# Power_input.net
KiCad netlist of a schematic drawn in Altium Designer
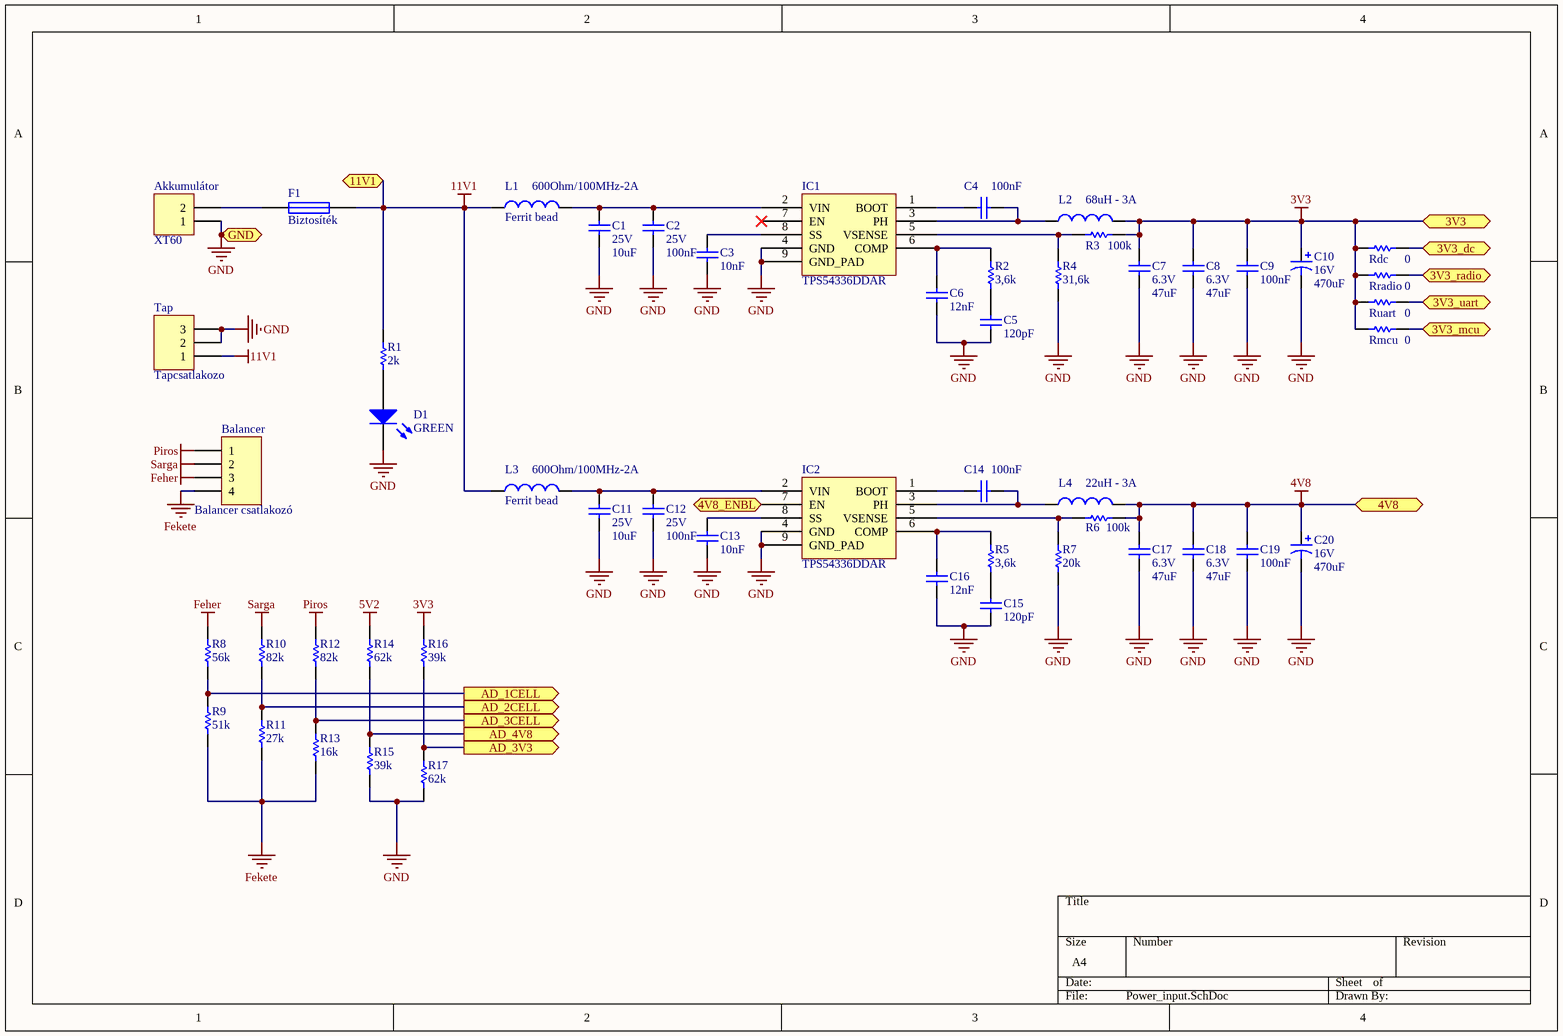
[diagram p0: Power_input.SchDoc]

(export (version "E")
  (design (tool "Eeschema 10.0.6"))
  (components
    (comp (ref "Akkumulátor")
      (value "XT60")
      (footprint "XT60")
      (description "Header, 2-Pin")
      (fields (field (name "PUBLISHER") "Altium Limited"))
      (libsource (lib "Miscellaneous Connectors") (part "Header 2"))
    )
    (comp (ref "Balancer")
      (value "Balancer csatlakozó")
      (footprint "FP_CONN4_TUSKE_254MM")
      (description "Header, 4-Pin")
      (fields (field (name "PUBLISHER") "Altium Limited"))
      (libsource (lib "Miscellaneous Connectors") (part "Header 4"))
    )
    (comp (ref "C1")
      (value "25V")
      (footprint "FP_1206_CAP_125")
      (description "Capacitor")
      (fields (field (name "ALTIUM_VALUE") "10uF") (field (name "PUBLISHER") "Altium Limited"))
      (libsource (lib "Miscellaneous Devices") (part "Cap"))
    )
    (comp (ref "C2")
      (value "25V")
      (footprint "FP_1206_CAP_125")
      (description "Capacitor")
      (fields (field (name "ALTIUM_VALUE") "100nF") (field (name "PUBLISHER") "Altium Limited"))
      (libsource (lib "Miscellaneous Devices") (part "Cap"))
    )
    (comp (ref "C3")
      (value "10nF")
      (footprint "FP_0603_CAP_080")
      (description "Capacitor")
      (fields (field (name "Comment") "Cap") (field (name "PUBLISHER") "Altium Limited"))
      (libsource (lib "Miscellaneous Devices") (part "Cap"))
    )
    (comp (ref "C4")
      (value "100nF")
      (footprint "FP_1206_CAP_125")
      (description "Capacitor")
      (fields (field (name "Comment") "Cap") (field (name "PUBLISHER") "Altium Limited"))
      (libsource (lib "Miscellaneous Devices") (part "Cap"))
    )
    (comp (ref "C5")
      (value "120pF")
      (footprint "FP_0603_CAP_080")
      (description "Capacitor")
      (fields (field (name "PUBLISHER") "Altium Limited"))
      (libsource (lib "Miscellaneous Devices") (part "Cap"))
    )
    (comp (ref "C6")
      (value "12nF")
      (footprint "FP_0603_CAP_080")
      (description "Capacitor")
      (fields (field (name "PUBLISHER") "Altium Limited"))
      (libsource (lib "Miscellaneous Devices") (part "Cap"))
    )
    (comp (ref "C7")
      (value "6.3V")
      (footprint "FP_1206_CAP_125")
      (description "Capacitor")
      (fields (field (name "ALTIUM_VALUE") "47uF") (field (name "PUBLISHER") "Altium Limited"))
      (libsource (lib "Miscellaneous Devices") (part "Cap"))
    )
    (comp (ref "C8")
      (value "6.3V")
      (footprint "FP_1206_CAP_125")
      (description "Capacitor")
      (fields (field (name "ALTIUM_VALUE") "47uF") (field (name "PUBLISHER") "Altium Limited"))
      (libsource (lib "Miscellaneous Devices") (part "Cap"))
    )
    (comp (ref "C9")
      (value "100nF")
      (footprint "FP_1206_CAP_125")
      (description "Capacitor")
      (fields (field (name "Comment") "Cap") (field (name "PUBLISHER") "Altium Limited"))
      (libsource (lib "Miscellaneous Devices") (part "Cap"))
    )
    (comp (ref "C10")
      (value "16V")
      (footprint "power_cap_10mm")
      (description "Polarized Capacitor (Radial)")
      (fields (field (name "ALTIUM_VALUE") "470uF") (field (name "PUBLISHER") "Altium Limited"))
      (libsource (lib "Miscellaneous Devices") (part "Cap Pol1"))
    )
    (comp (ref "C11")
      (value "25V")
      (footprint "FP_1206_CAP_125")
      (description "Capacitor")
      (fields (field (name "ALTIUM_VALUE") "10uF") (field (name "PUBLISHER") "Altium Limited"))
      (libsource (lib "Miscellaneous Devices") (part "Cap"))
    )
    (comp (ref "C12")
      (value "25V")
      (footprint "FP_1206_CAP_125")
      (description "Capacitor")
      (fields (field (name "ALTIUM_VALUE") "100nF") (field (name "PUBLISHER") "Altium Limited"))
      (libsource (lib "Miscellaneous Devices") (part "Cap"))
    )
    (comp (ref "C13")
      (value "10nF")
      (footprint "FP_0603_CAP_080")
      (description "Capacitor")
      (fields (field (name "Comment") "Cap") (field (name "PUBLISHER") "Altium Limited"))
      (libsource (lib "Miscellaneous Devices") (part "Cap"))
    )
    (comp (ref "C14")
      (value "100nF")
      (footprint "FP_1206_CAP_125")
      (description "Capacitor")
      (fields (field (name "Comment") "Cap") (field (name "PUBLISHER") "Altium Limited"))
      (libsource (lib "Miscellaneous Devices") (part "Cap"))
    )
    (comp (ref "C15")
      (value "120pF")
      (footprint "FP_0603_CAP_080")
      (description "Capacitor")
      (fields (field (name "PUBLISHER") "Altium Limited"))
      (libsource (lib "Miscellaneous Devices") (part "Cap"))
    )
    (comp (ref "C16")
      (value "12nF")
      (footprint "FP_0603_CAP_080")
      (description "Capacitor")
      (fields (field (name "PUBLISHER") "Altium Limited"))
      (libsource (lib "Miscellaneous Devices") (part "Cap"))
    )
    (comp (ref "C17")
      (value "6.3V")
      (footprint "FP_1206_CAP_125")
      (description "Capacitor")
      (fields (field (name "ALTIUM_VALUE") "47uF") (field (name "PUBLISHER") "Altium Limited"))
      (libsource (lib "Miscellaneous Devices") (part "Cap"))
    )
    (comp (ref "C18")
      (value "6.3V")
      (footprint "FP_1206_CAP_125")
      (description "Capacitor")
      (fields (field (name "ALTIUM_VALUE") "47uF") (field (name "PUBLISHER") "Altium Limited"))
      (libsource (lib "Miscellaneous Devices") (part "Cap"))
    )
    (comp (ref "C19")
      (value "100nF")
      (footprint "FP_1206_CAP_125")
      (description "Capacitor")
      (fields (field (name "Comment") "Cap") (field (name "PUBLISHER") "Altium Limited"))
      (libsource (lib "Miscellaneous Devices") (part "Cap"))
    )
    (comp (ref "C20")
      (value "16V")
      (footprint "power_cap_10mm")
      (description "Polarized Capacitor (Radial)")
      (fields (field (name "ALTIUM_VALUE") "470uF") (field (name "PUBLISHER") "Altium Limited"))
      (libsource (lib "Miscellaneous Devices") (part "Cap Pol1"))
    )
    (comp (ref "D1")
      (value "GREEN")
      (footprint "FP_1206_CAP_160")
      (description "Typical INFRARED GaAs LED")
      (fields (field (name "PUBLISHER") "Altium Limited"))
      (libsource (lib "Miscellaneous Devices") (part "LED0"))
    )
    (comp (ref "F1")
      (value "Biztosíték")
      (footprint "autosarus_foglalat")
      (description "Fuse")
      (fields (field (name "PUBLISHER") "Altium Limited"))
      (libsource (lib "Miscellaneous Devices") (part "Fuse 1"))
    )
    (comp (ref "IC1")
      (value "TPS54336DDAR")
      (footprint "SOIC8_thermal_pad")
      (libsource (lib "diploma") (part "TPS54336"))
    )
    (comp (ref "IC2")
      (value "TPS54336DDAR")
      (footprint "SOIC8_thermal_pad")
      (libsource (lib "diploma") (part "TPS54336"))
    )
    (comp (ref "L1")
      (value "Ferrit bead")
      (footprint "FP_0805_IND")
      (description "Inductor")
      (fields (field (name "ALTIUM_VALUE") "600Ohm/100MHz-2A") (field (name "PUBLISHER") "Altium Limited"))
      (libsource (lib "Miscellaneous Devices") (part "Inductor"))
    )
    (comp (ref "L2")
      (value "68uH - 3A")
      (footprint "power_inductor")
      (description "Inductor")
      (fields (field (name "PUBLISHER") "Altium Limited"))
      (libsource (lib "Miscellaneous Devices") (part "Inductor"))
    )
    (comp (ref "L3")
      (value "Ferrit bead")
      (footprint "FP_0805_IND")
      (description "Inductor")
      (fields (field (name "ALTIUM_VALUE") "600Ohm/100MHz-2A") (field (name "PUBLISHER") "Altium Limited"))
      (libsource (lib "Miscellaneous Devices") (part "Inductor"))
    )
    (comp (ref "L4")
      (value "22uH - 3A")
      (footprint "power_inductor")
      (description "Inductor")
      (fields (field (name "PUBLISHER") "Altium Limited"))
      (libsource (lib "Miscellaneous Devices") (part "Inductor"))
    )
    (comp (ref "R1")
      (value "2k")
      (footprint "FP_0603_RES")
      (description "Resistor")
      (fields (field (name "Comment") "Res1") (field (name "PUBLISHER") "Altium Limited"))
      (libsource (lib "Miscellaneous Devices") (part "Res1"))
    )
    (comp (ref "R2")
      (value "3,6k")
      (footprint "FP_0603_RES")
      (description "Resistor")
      (fields (field (name "Comment") "Res1") (field (name "PUBLISHER") "Altium Limited"))
      (libsource (lib "Miscellaneous Devices") (part "Res1"))
    )
    (comp (ref "R3")
      (value "100k")
      (footprint "FP_0603_RES")
      (description "Resistor")
      (fields (field (name "Comment") "Res1") (field (name "PUBLISHER") "Altium Limited"))
      (libsource (lib "Miscellaneous Devices") (part "Res1"))
    )
    (comp (ref "R4")
      (value "31,6k")
      (footprint "FP_0603_RES")
      (description "Resistor")
      (fields (field (name "Comment") "Res1") (field (name "PUBLISHER") "Altium Limited"))
      (libsource (lib "Miscellaneous Devices") (part "Res1"))
    )
    (comp (ref "R5")
      (value "3,6k")
      (footprint "FP_0603_RES")
      (description "Resistor")
      (fields (field (name "Comment") "Res1") (field (name "PUBLISHER") "Altium Limited"))
      (libsource (lib "Miscellaneous Devices") (part "Res1"))
    )
    (comp (ref "R6")
      (value "100k")
      (footprint "FP_0603_RES")
      (description "Resistor")
      (fields (field (name "Comment") "Res1") (field (name "PUBLISHER") "Altium Limited"))
      (libsource (lib "Miscellaneous Devices") (part "Res1"))
    )
    (comp (ref "R7")
      (value "20k")
      (footprint "FP_0603_RES")
      (description "Resistor")
      (fields (field (name "Comment") "Res1") (field (name "PUBLISHER") "Altium Limited"))
      (libsource (lib "Miscellaneous Devices") (part "Res1"))
    )
    (comp (ref "R8")
      (value "56k")
      (footprint "FP_0603_RES")
      (description "Resistor")
      (fields (field (name "Comment") "Res1") (field (name "PUBLISHER") "Altium Limited"))
      (libsource (lib "Miscellaneous Devices") (part "Res1"))
    )
    (comp (ref "R9")
      (value "51k")
      (footprint "FP_0603_RES")
      (description "Resistor")
      (fields (field (name "Comment") "Res1") (field (name "PUBLISHER") "Altium Limited"))
      (libsource (lib "Miscellaneous Devices") (part "Res1"))
    )
    (comp (ref "R10")
      (value "82k")
      (footprint "FP_0603_RES")
      (description "Resistor")
      (fields (field (name "Comment") "Res1") (field (name "PUBLISHER") "Altium Limited"))
      (libsource (lib "Miscellaneous Devices") (part "Res1"))
    )
    (comp (ref "R11")
      (value "27k")
      (footprint "FP_0603_RES")
      (description "Resistor")
      (fields (field (name "Comment") "Res1") (field (name "PUBLISHER") "Altium Limited"))
      (libsource (lib "Miscellaneous Devices") (part "Res1"))
    )
    (comp (ref "R12")
      (value "82k")
      (footprint "FP_0603_RES")
      (description "Resistor")
      (fields (field (name "Comment") "Res1") (field (name "PUBLISHER") "Altium Limited"))
      (libsource (lib "Miscellaneous Devices") (part "Res1"))
    )
    (comp (ref "R13")
      (value "16k")
      (footprint "FP_0603_RES")
      (description "Resistor")
      (fields (field (name "Comment") "Res1") (field (name "PUBLISHER") "Altium Limited"))
      (libsource (lib "Miscellaneous Devices") (part "Res1"))
    )
    (comp (ref "R14")
      (value "62k")
      (footprint "FP_0603_RES")
      (description "Resistor")
      (fields (field (name "Comment") "Res1") (field (name "PUBLISHER") "Altium Limited"))
      (libsource (lib "Miscellaneous Devices") (part "Res1"))
    )
    (comp (ref "R15")
      (value "39k")
      (footprint "FP_0603_RES")
      (description "Resistor")
      (fields (field (name "Comment") "Res1") (field (name "PUBLISHER") "Altium Limited"))
      (libsource (lib "Miscellaneous Devices") (part "Res1"))
    )
    (comp (ref "R16")
      (value "39k")
      (footprint "FP_0603_RES")
      (description "Resistor")
      (fields (field (name "Comment") "Res1") (field (name "PUBLISHER") "Altium Limited"))
      (libsource (lib "Miscellaneous Devices") (part "Res1"))
    )
    (comp (ref "R17")
      (value "62k")
      (footprint "FP_0603_RES")
      (description "Resistor")
      (fields (field (name "Comment") "Res1") (field (name "PUBLISHER") "Altium Limited"))
      (libsource (lib "Miscellaneous Devices") (part "Res1"))
    )
    (comp (ref "Rdc")
      (value "0")
      (footprint "FP_1206_RES")
      (description "Resistor")
      (fields (field (name "Comment") "Res1") (field (name "PUBLISHER") "Altium Limited"))
      (libsource (lib "Miscellaneous Devices") (part "Res1"))
    )
    (comp (ref "Rmcu")
      (value "0")
      (footprint "FP_1206_RES")
      (description "Resistor")
      (fields (field (name "Comment") "Res1") (field (name "PUBLISHER") "Altium Limited"))
      (libsource (lib "Miscellaneous Devices") (part "Res1"))
    )
    (comp (ref "Rradio")
      (value "0")
      (footprint "FP_1206_RES")
      (description "Resistor")
      (fields (field (name "Comment") "Res1") (field (name "PUBLISHER") "Altium Limited"))
      (libsource (lib "Miscellaneous Devices") (part "Res1"))
    )
    (comp (ref "Ruart")
      (value "0")
      (footprint "FP_1206_RES")
      (description "Resistor")
      (fields (field (name "Comment") "Res1") (field (name "PUBLISHER") "Altium Limited"))
      (libsource (lib "Miscellaneous Devices") (part "Res1"))
    )
    (comp (ref "Tap")
      (value "Tapcsatlakozo")
      (footprint "FP_DC_TAP_ANYA")
      (description "Header, 3-Pin")
      (fields (field (name "PUBLISHER") "Altium Limited"))
      (libsource (lib "Miscellaneous Connectors") (part "Header 3"))
    )
  )
  (nets
    (net (code "1") (name "/3V3_dc") (class "Default")
      (node (ref "Rdc") (pin "1") (pinfunction "1_1") (pintype "passive"))
    )
    (net (code "2") (name "/3V3_mcu") (class "Default")
      (node (ref "Rmcu") (pin "1") (pinfunction "1_1") (pintype "passive"))
    )
    (net (code "3") (name "/3V3_radio") (class "Default")
      (node (ref "Rradio") (pin "1") (pinfunction "1_1") (pintype "passive"))
    )
    (net (code "4") (name "/3V3_uart") (class "Default")
      (node (ref "Ruart") (pin "1") (pinfunction "1_1") (pintype "passive"))
    )
    (net (code "5") (name "/4V8_ENBL") (class "Default")
      (node (ref "IC2") (pin "7") (pinfunction "EN_7") (pintype "passive"))
    )
    (net (code "6") (name "/AD_1CELL") (class "Default")
      (node (ref "R8") (pin "1") (pinfunction "1_1") (pintype "passive"))
      (node (ref "R9") (pin "2") (pinfunction "2_2") (pintype "passive"))
    )
    (net (code "7") (name "/AD_2CELL") (class "Default")
      (node (ref "R10") (pin "1") (pinfunction "1_1") (pintype "passive"))
      (node (ref "R11") (pin "2") (pinfunction "2_2") (pintype "passive"))
    )
    (net (code "8") (name "/AD_3CELL") (class "Default")
      (node (ref "R12") (pin "1") (pinfunction "1_1") (pintype "passive"))
      (node (ref "R13") (pin "2") (pinfunction "2_2") (pintype "passive"))
    )
    (net (code "9") (name "/AD_3V3") (class "Default")
      (node (ref "R16") (pin "1") (pinfunction "1_1") (pintype "passive"))
      (node (ref "R17") (pin "2") (pinfunction "2_2") (pintype "passive"))
    )
    (net (code "10") (name "/AD_4V8") (class "Default")
      (node (ref "R14") (pin "1") (pinfunction "1_1") (pintype "passive"))
      (node (ref "R15") (pin "2") (pinfunction "2_2") (pintype "passive"))
    )
    (net (code "11") (name "3V3") (class "Default")
      (node (ref "C10") (pin "1") (pinfunction "1_1") (pintype "passive"))
      (node (ref "C7") (pin "1") (pinfunction "1_1") (pintype "passive"))
      (node (ref "C8") (pin "1") (pinfunction "1_1") (pintype "passive"))
      (node (ref "C9") (pin "1") (pinfunction "1_1") (pintype "passive"))
      (node (ref "L2") (pin "2") (pinfunction "2_2") (pintype "passive"))
      (node (ref "R16") (pin "2") (pinfunction "2_2") (pintype "passive"))
      (node (ref "R3") (pin "1") (pinfunction "1_1") (pintype "passive"))
      (node (ref "Rdc") (pin "2") (pinfunction "2_2") (pintype "passive"))
      (node (ref "Rmcu") (pin "2") (pinfunction "2_2") (pintype "passive"))
      (node (ref "Rradio") (pin "2") (pinfunction "2_2") (pintype "passive"))
      (node (ref "Ruart") (pin "2") (pinfunction "2_2") (pintype "passive"))
    )
    (net (code "12") (name "4V8") (class "Default")
      (node (ref "C17") (pin "1") (pinfunction "1_1") (pintype "passive"))
      (node (ref "C18") (pin "1") (pinfunction "1_1") (pintype "passive"))
      (node (ref "C19") (pin "1") (pinfunction "1_1") (pintype "passive"))
      (node (ref "C20") (pin "1") (pinfunction "1_1") (pintype "passive"))
      (node (ref "L4") (pin "2") (pinfunction "2_2") (pintype "passive"))
      (node (ref "R6") (pin "1") (pinfunction "1_1") (pintype "passive"))
    )
    (net (code "13") (name "5V2") (class "Default")
      (node (ref "R14") (pin "2") (pinfunction "2_2") (pintype "passive"))
    )
    (net (code "14") (name "11V1") (class "Default")
      (node (ref "F1") (pin "2") (pinfunction "2_2") (pintype "passive"))
      (node (ref "L1") (pin "1") (pinfunction "1_1") (pintype "passive"))
      (node (ref "L3") (pin "1") (pinfunction "1_1") (pintype "passive"))
      (node (ref "R1") (pin "2") (pinfunction "2_2") (pintype "passive"))
      (node (ref "Tap") (pin "1") (pinfunction "1_1") (pintype "passive"))
    )
    (net (code "15") (name "Feher") (class "Default")
      (node (ref "Balancer") (pin "3") (pinfunction "3_3") (pintype "passive"))
      (node (ref "R8") (pin "2") (pinfunction "2_2") (pintype "passive"))
    )
    (net (code "16") (name "Fekete") (class "Default")
      (node (ref "Balancer") (pin "4") (pinfunction "4_4") (pintype "passive"))
      (node (ref "R11") (pin "1") (pinfunction "1_1") (pintype "passive"))
      (node (ref "R13") (pin "1") (pinfunction "1_1") (pintype "passive"))
      (node (ref "R9") (pin "1") (pinfunction "1_1") (pintype "passive"))
    )
    (net (code "17") (name "GND") (class "Default")
      (node (ref "Akkumulátor") (pin "1") (pinfunction "1_1") (pintype "passive"))
      (node (ref "C1") (pin "2") (pinfunction "2_2") (pintype "passive"))
      (node (ref "C10") (pin "2") (pinfunction "2_2") (pintype "passive"))
      (node (ref "C11") (pin "2") (pinfunction "2_2") (pintype "passive"))
      (node (ref "C12") (pin "2") (pinfunction "2_2") (pintype "passive"))
      (node (ref "C13") (pin "2") (pinfunction "2_2") (pintype "passive"))
      (node (ref "C15") (pin "2") (pinfunction "2_2") (pintype "passive"))
      (node (ref "C16") (pin "2") (pinfunction "2_2") (pintype "passive"))
      (node (ref "C17") (pin "2") (pinfunction "2_2") (pintype "passive"))
      (node (ref "C18") (pin "2") (pinfunction "2_2") (pintype "passive"))
      (node (ref "C19") (pin "2") (pinfunction "2_2") (pintype "passive"))
      (node (ref "C2") (pin "2") (pinfunction "2_2") (pintype "passive"))
      (node (ref "C20") (pin "2") (pinfunction "2_2") (pintype "passive"))
      (node (ref "C3") (pin "2") (pinfunction "2_2") (pintype "passive"))
      (node (ref "C5") (pin "2") (pinfunction "2_2") (pintype "passive"))
      (node (ref "C6") (pin "2") (pinfunction "2_2") (pintype "passive"))
      (node (ref "C7") (pin "2") (pinfunction "2_2") (pintype "passive"))
      (node (ref "C8") (pin "2") (pinfunction "2_2") (pintype "passive"))
      (node (ref "C9") (pin "2") (pinfunction "2_2") (pintype "passive"))
      (node (ref "D1") (pin "2") (pinfunction "K_2") (pintype "passive"))
      (node (ref "IC1") (pin "4") (pinfunction "GND_4") (pintype "passive"))
      (node (ref "IC1") (pin "9") (pinfunction "GND_PAD_9") (pintype "passive"))
      (node (ref "IC2") (pin "4") (pinfunction "GND_4") (pintype "passive"))
      (node (ref "IC2") (pin "9") (pinfunction "GND_PAD_9") (pintype "passive"))
      (node (ref "R15") (pin "1") (pinfunction "1_1") (pintype "passive"))
      (node (ref "R17") (pin "1") (pinfunction "1_1") (pintype "passive"))
      (node (ref "R4") (pin "1") (pinfunction "1_1") (pintype "passive"))
      (node (ref "R7") (pin "1") (pinfunction "1_1") (pintype "passive"))
      (node (ref "Tap") (pin "2") (pinfunction "2_2") (pintype "passive"))
      (node (ref "Tap") (pin "3") (pinfunction "3_3") (pintype "passive"))
    )
    (net (code "18") (name "Net-(Akkumulátor-Pad2)") (class "Default")
      (node (ref "Akkumulátor") (pin "2") (pinfunction "2_2") (pintype "passive"))
      (node (ref "F1") (pin "1") (pinfunction "1_1") (pintype "passive"))
    )
    (net (code "19") (name "Net-(C5-Pad1)") (class "Default")
      (node (ref "C5") (pin "1") (pinfunction "1_1") (pintype "passive"))
      (node (ref "R2") (pin "1") (pinfunction "1_1") (pintype "passive"))
    )
    (net (code "20") (name "Net-(C15-Pad1)") (class "Default")
      (node (ref "C15") (pin "1") (pinfunction "1_1") (pintype "passive"))
      (node (ref "R5") (pin "1") (pinfunction "1_1") (pintype "passive"))
    )
    (net (code "21") (name "Net-(D1-A)") (class "Default")
      (node (ref "D1") (pin "1") (pinfunction "A_1") (pintype "passive"))
      (node (ref "R1") (pin "1") (pinfunction "1_1") (pintype "passive"))
    )
    (net (code "22") (name "Net-(IC1-BOOT)") (class "Default")
      (node (ref "C4") (pin "1") (pinfunction "1_1") (pintype "passive"))
      (node (ref "IC1") (pin "1") (pinfunction "BOOT_1") (pintype "passive"))
    )
    (net (code "23") (name "Net-(IC1-COMP)") (class "Default")
      (node (ref "C6") (pin "1") (pinfunction "1_1") (pintype "passive"))
      (node (ref "IC1") (pin "6") (pinfunction "COMP_6") (pintype "passive"))
      (node (ref "R2") (pin "2") (pinfunction "2_2") (pintype "passive"))
    )
    (net (code "24") (name "Net-(IC1-PH)") (class "Default")
      (node (ref "C4") (pin "2") (pinfunction "2_2") (pintype "passive"))
      (node (ref "IC1") (pin "3") (pinfunction "PH_3") (pintype "passive"))
      (node (ref "L2") (pin "1") (pinfunction "1_1") (pintype "passive"))
    )
    (net (code "25") (name "Net-(IC1-SS)") (class "Default")
      (node (ref "C3") (pin "1") (pinfunction "1_1") (pintype "passive"))
      (node (ref "IC1") (pin "8") (pinfunction "SS_8") (pintype "passive"))
    )
    (net (code "26") (name "Net-(IC1-VIN)") (class "Default")
      (node (ref "C1") (pin "1") (pinfunction "1_1") (pintype "passive"))
      (node (ref "C2") (pin "1") (pinfunction "1_1") (pintype "passive"))
      (node (ref "IC1") (pin "2") (pinfunction "VIN_2") (pintype "passive"))
      (node (ref "L1") (pin "2") (pinfunction "2_2") (pintype "passive"))
    )
    (net (code "27") (name "Net-(IC1-VSENSE)") (class "Default")
      (node (ref "IC1") (pin "5") (pinfunction "VSENSE_5") (pintype "passive"))
      (node (ref "R3") (pin "2") (pinfunction "2_2") (pintype "passive"))
      (node (ref "R4") (pin "2") (pinfunction "2_2") (pintype "passive"))
    )
    (net (code "28") (name "Net-(IC2-BOOT)") (class "Default")
      (node (ref "C14") (pin "1") (pinfunction "1_1") (pintype "passive"))
      (node (ref "IC2") (pin "1") (pinfunction "BOOT_1") (pintype "passive"))
    )
    (net (code "29") (name "Net-(IC2-COMP)") (class "Default")
      (node (ref "C16") (pin "1") (pinfunction "1_1") (pintype "passive"))
      (node (ref "IC2") (pin "6") (pinfunction "COMP_6") (pintype "passive"))
      (node (ref "R5") (pin "2") (pinfunction "2_2") (pintype "passive"))
    )
    (net (code "30") (name "Net-(IC2-PH)") (class "Default")
      (node (ref "C14") (pin "2") (pinfunction "2_2") (pintype "passive"))
      (node (ref "IC2") (pin "3") (pinfunction "PH_3") (pintype "passive"))
      (node (ref "L4") (pin "1") (pinfunction "1_1") (pintype "passive"))
    )
    (net (code "31") (name "Net-(IC2-SS)") (class "Default")
      (node (ref "C13") (pin "1") (pinfunction "1_1") (pintype "passive"))
      (node (ref "IC2") (pin "8") (pinfunction "SS_8") (pintype "passive"))
    )
    (net (code "32") (name "Net-(IC2-VIN)") (class "Default")
      (node (ref "C11") (pin "1") (pinfunction "1_1") (pintype "passive"))
      (node (ref "C12") (pin "1") (pinfunction "1_1") (pintype "passive"))
      (node (ref "IC2") (pin "2") (pinfunction "VIN_2") (pintype "passive"))
      (node (ref "L3") (pin "2") (pinfunction "2_2") (pintype "passive"))
    )
    (net (code "33") (name "Net-(IC2-VSENSE)") (class "Default")
      (node (ref "IC2") (pin "5") (pinfunction "VSENSE_5") (pintype "passive"))
      (node (ref "R6") (pin "2") (pinfunction "2_2") (pintype "passive"))
      (node (ref "R7") (pin "2") (pinfunction "2_2") (pintype "passive"))
    )
    (net (code "34") (name "Piros") (class "Default")
      (node (ref "Balancer") (pin "1") (pinfunction "1_1") (pintype "passive"))
      (node (ref "R12") (pin "2") (pinfunction "2_2") (pintype "passive"))
    )
    (net (code "35") (name "Sarga") (class "Default")
      (node (ref "Balancer") (pin "2") (pinfunction "2_2") (pintype "passive"))
      (node (ref "R10") (pin "2") (pinfunction "2_2") (pintype "passive"))
    )
    (net (code "36") (name "unconnected-(IC1-EN-Pad7)") (class "Default")
      (node (ref "IC1") (pin "7") (pinfunction "EN_7") (pintype "passive+no_connect"))
    )
  )
)
